# USBHUB_USB2512.net
KiCad netlist of a schematic drawn in Altium Designer
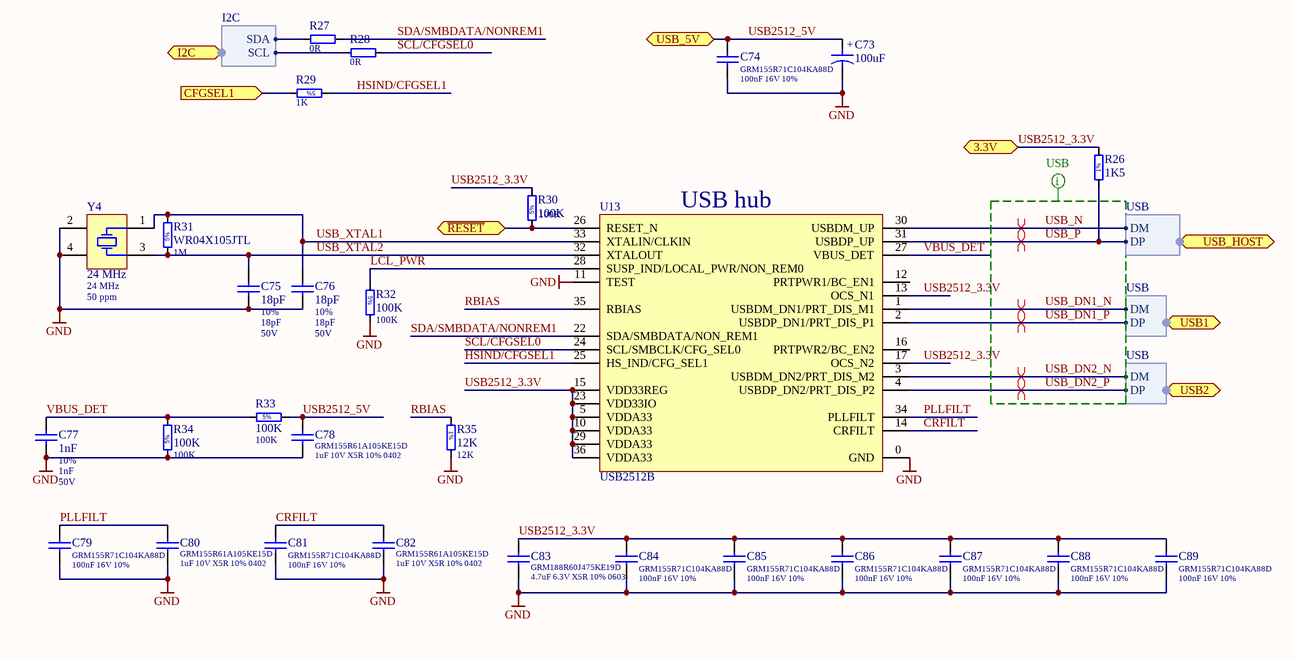
[diagram p0: USBHUB_USB2512.SchDoc]

(export (version "E")
  (design (tool "Eeschema 10.0.6"))
  (components
    (comp (ref "C73")
      (value "100uF")
      (footprint "TANTALUM:C")
      (description "Polarized capacitor")
      (fields (field (name "VOLTAGE") "50V") (field (name "TOLERANCE") "10%"))
      (libsource (lib "Passive") (part "CapacitorTANT"))
    )
    (comp (ref "C74")
      (value "GRM155R71C104KA88D")
      (footprint "CAP_SMD:0402")
      (description "Ceramic capacitor")
      (fields
        (field (name "VOLTAGE") "16V")
        (field (name "TOLERANCE") "10%")
        (field (name "ALTIUM_VALUE") "100nF 16V 10%")
      )
      (libsource (lib "") (part "Capacitor ceramic_1"))
    )
    (comp (ref "C75")
      (value "18pF")
      (footprint "CHIP_SMD:0402C")
      (description "Ceramic capacitor")
      (fields
        (field (name "TOLERANCE") "10%")
        (field (name "ALTIUM_VALUE") "18pF")
        (field (name "VOLTAGE") "50V")
      )
      (libsource (lib "") (part "Capacitor ceramic_1"))
    )
    (comp (ref "C76")
      (value "18pF")
      (footprint "CHIP_SMD:0402C")
      (description "Ceramic capacitor")
      (fields
        (field (name "TOLERANCE") "10%")
        (field (name "ALTIUM_VALUE") "18pF")
        (field (name "VOLTAGE") "50V")
      )
      (libsource (lib "") (part "Capacitor ceramic_1"))
    )
    (comp (ref "C77")
      (value "1nF")
      (footprint "CHIP_SMD:0402C")
      (description "Ceramic capacitor")
      (fields
        (field (name "TOLERANCE") "10%")
        (field (name "ALTIUM_VALUE") "1nF")
        (field (name "VOLTAGE") "50V")
      )
      (libsource (lib "") (part "Capacitor ceramic_1"))
    )
    (comp (ref "C78")
      (value "GRM155R61A105KE15D")
      (footprint "CAP_SMD:0402")
      (description "Ceramic capacitor")
      (fields
        (field (name "VOLTAGE") "10V")
        (field (name "TOLERANCE") "10%")
        (field (name "ALTIUM_VALUE") "1uF 10V X5R 10% ")
      )
      (libsource (lib "Passive") (part "Capacitor ceramic"))
    )
    (comp (ref "C79")
      (value "GRM155R71C104KA88D")
      (footprint "CAP_SMD:0402")
      (description "Ceramic capacitor")
      (fields
        (field (name "VOLTAGE") "16V")
        (field (name "TOLERANCE") "10%")
        (field (name "ALTIUM_VALUE") "100nF 16V 10%")
      )
      (libsource (lib "") (part "Capacitor ceramic_1"))
    )
    (comp (ref "C80")
      (value "GRM155R61A105KE15D")
      (footprint "CAP_SMD:0402")
      (description "Ceramic capacitor")
      (fields
        (field (name "VOLTAGE") "10V")
        (field (name "TOLERANCE") "10%")
        (field (name "ALTIUM_VALUE") "1uF 10V X5R 10% ")
      )
      (libsource (lib "Passive") (part "Capacitor ceramic"))
    )
    (comp (ref "C81")
      (value "GRM155R71C104KA88D")
      (footprint "CAP_SMD:0402")
      (description "Ceramic capacitor")
      (fields
        (field (name "VOLTAGE") "16V")
        (field (name "TOLERANCE") "10%")
        (field (name "ALTIUM_VALUE") "100nF 16V 10%")
      )
      (libsource (lib "") (part "Capacitor ceramic_1"))
    )
    (comp (ref "C82")
      (value "GRM155R61A105KE15D")
      (footprint "CAP_SMD:0402")
      (description "Ceramic capacitor")
      (fields
        (field (name "VOLTAGE") "10V")
        (field (name "TOLERANCE") "10%")
        (field (name "ALTIUM_VALUE") "1uF 10V X5R 10% ")
      )
      (libsource (lib "Passive") (part "Capacitor ceramic"))
    )
    (comp (ref "C83")
      (value "GRM188R60J475KE19D")
      (footprint "CAP_SMD:0603")
      (description "Ceramic capacitor")
      (fields
        (field (name "VOLTAGE") "6.3V")
        (field (name "TOLERANCE") "10%")
        (field (name "ALTIUM_VALUE") "4.7uF 6.3V X5R 10% ")
      )
      (libsource (lib "Passive") (part "Capacitor ceramic"))
    )
    (comp (ref "C84")
      (value "GRM155R71C104KA88D")
      (footprint "CAP_SMD:0402")
      (description "Ceramic capacitor")
      (fields
        (field (name "VOLTAGE") "16V")
        (field (name "TOLERANCE") "10%")
        (field (name "ALTIUM_VALUE") "100nF 16V 10%")
      )
      (libsource (lib "") (part "Capacitor ceramic_1"))
    )
    (comp (ref "C85")
      (value "GRM155R71C104KA88D")
      (footprint "CAP_SMD:0402")
      (description "Ceramic capacitor")
      (fields
        (field (name "VOLTAGE") "16V")
        (field (name "TOLERANCE") "10%")
        (field (name "ALTIUM_VALUE") "100nF 16V 10%")
      )
      (libsource (lib "") (part "Capacitor ceramic_1"))
    )
    (comp (ref "C86")
      (value "GRM155R71C104KA88D")
      (footprint "CAP_SMD:0402")
      (description "Ceramic capacitor")
      (fields
        (field (name "VOLTAGE") "16V")
        (field (name "TOLERANCE") "10%")
        (field (name "ALTIUM_VALUE") "100nF 16V 10%")
      )
      (libsource (lib "") (part "Capacitor ceramic_1"))
    )
    (comp (ref "C87")
      (value "GRM155R71C104KA88D")
      (footprint "CAP_SMD:0402")
      (description "Ceramic capacitor")
      (fields
        (field (name "VOLTAGE") "16V")
        (field (name "TOLERANCE") "10%")
        (field (name "ALTIUM_VALUE") "100nF 16V 10%")
      )
      (libsource (lib "") (part "Capacitor ceramic_1"))
    )
    (comp (ref "C88")
      (value "GRM155R71C104KA88D")
      (footprint "CAP_SMD:0402")
      (description "Ceramic capacitor")
      (fields
        (field (name "VOLTAGE") "16V")
        (field (name "TOLERANCE") "10%")
        (field (name "ALTIUM_VALUE") "100nF 16V 10%")
      )
      (libsource (lib "") (part "Capacitor ceramic_1"))
    )
    (comp (ref "C89")
      (value "GRM155R71C104KA88D")
      (footprint "CAP_SMD:0402")
      (description "Ceramic capacitor")
      (fields
        (field (name "VOLTAGE") "16V")
        (field (name "TOLERANCE") "10%")
        (field (name "ALTIUM_VALUE") "100nF 16V 10%")
      )
      (libsource (lib "") (part "Capacitor ceramic_1"))
    )
    (comp (ref "R26")
      (value "1K5")
      (footprint "CHIP_SMD:0402R")
      (description "Thin Film Chip Resistor")
      (fields (field (name "POWER") "0.1 W") (field (name "TOLERANCE") "1%"))
      (libsource (lib "Passive") (part "Resistor 1%"))
    )
    (comp (ref "R27")
      (value "0R")
      (footprint "CHIP_SMD:0402R")
      (description "Thin Film Resistor Jumper")
      (fields (field (name "POWER") "0.1 W") (field (name "Comment") "Resistor jumper"))
      (libsource (lib "Passive") (part "Resistor jumper"))
    )
    (comp (ref "R28")
      (value "0R")
      (footprint "CHIP_SMD:0402R")
      (description "Thin Film Resistor Jumper")
      (fields (field (name "POWER") "0.1 W") (field (name "Comment") "Resistor jumper"))
      (libsource (lib "Passive") (part "Resistor jumper"))
    )
    (comp (ref "R29")
      (value "1K")
      (footprint "CHIP_SMD:0402R")
      (description "Thin Film Chip Resistor")
      (fields (field (name "POWER") "0.1 W") (field (name "TOLERANCE") "5%"))
      (libsource (lib "Passive") (part "Resistor"))
    )
    (comp (ref "R30")
      (value "100K")
      (footprint "CHIP_SMD:0402R")
      (description "Thin Film Chip Resistor")
      (fields
        (field (name "POWER") "0.1 W")
        (field (name "TOLERANCE") "5%")
        (field (name "ALTIUM_VALUE") "100K")
      )
      (libsource (lib "Passive") (part "Resistor"))
    )
    (comp (ref "R31")
      (value "WR04X105JTL")
      (footprint "CHIP_SMD:0402R")
      (description "Thin Film Chip Resistor")
      (fields
        (field (name "POWER") "0.1 W")
        (field (name "TOLERANCE") "5%")
        (field (name "ALTIUM_VALUE") "1M")
      )
      (libsource (lib "Passive") (part "Resistor"))
    )
    (comp (ref "R32")
      (value "100K")
      (footprint "CHIP_SMD:0402R")
      (description "Thin Film Chip Resistor")
      (fields
        (field (name "POWER") "0.1 W")
        (field (name "TOLERANCE") "5%")
        (field (name "ALTIUM_VALUE") "100K")
      )
      (libsource (lib "Passive") (part "Resistor"))
    )
    (comp (ref "R33")
      (value "100K")
      (footprint "CHIP_SMD:0402R")
      (description "Thin Film Chip Resistor")
      (fields
        (field (name "POWER") "0.1 W")
        (field (name "TOLERANCE") "5%")
        (field (name "ALTIUM_VALUE") "100K")
      )
      (libsource (lib "Passive") (part "Resistor"))
    )
    (comp (ref "R34")
      (value "100K")
      (footprint "CHIP_SMD:0402R")
      (description "Thin Film Chip Resistor")
      (fields
        (field (name "POWER") "0.1 W")
        (field (name "TOLERANCE") "5%")
        (field (name "ALTIUM_VALUE") "100K")
      )
      (libsource (lib "Passive") (part "Resistor"))
    )
    (comp (ref "R35")
      (value "12K")
      (footprint "CHIP_SMD:0402R")
      (description "Thin Film Chip Resistor")
      (fields
        (field (name "POWER") "0.1 W")
        (field (name "TOLERANCE") "1%")
        (field (name "ALTIUM_VALUE") "12K")
      )
      (libsource (lib "Passive") (part "Resistor"))
    )
    (comp (ref "U13")
      (value "USB2512B")
      (footprint "QFN_DFN:QFN-36-0.5-6x6_TP_5class")
      (description "USB 2.0 Hi-Speed Hub Controller")
      (libsource (lib "IC_USB") (part "USB2512B"))
    )
    (comp (ref "Y4")
      (value "24 MHz")
      (footprint "CRYSTAL_OSC:2025")
      (description "Quartz crystal")
      (fields (field (name "ALTIUM_VALUE") "24 MHz") (field (name "TOLERANCE") "50 ppm"))
      (libsource (lib "Crystal_Osc") (part "Quartz crystal"))
    )
  )
  (nets
    (net (code "3") (name "/CFGSEL1") (class "Default")
      (node (ref "R29") (pin "2") (pinfunction "2_2") (pintype "passive"))
    )
    (net (code "4") (name "/CRFILT") (class "Default")
      (node (ref "C81") (pin "1") (pinfunction "1_1") (pintype "passive"))
      (node (ref "C82") (pin "1") (pinfunction "1_1") (pintype "passive"))
      (node (ref "U13") (pin "14") (pinfunction "CRFILT_14") (pintype "passive"))
    )
    (net (code "5") (name "/HSIND{slash}CFGSEL1") (class "Default")
      (node (ref "R29") (pin "1") (pinfunction "1_1") (pintype "passive"))
      (node (ref "U13") (pin "25") (pinfunction "HS_IND/CFG_SEL1_25") (pintype "passive"))
    )
    (net (code "6") (name "/LCL_PWR") (class "Default")
      (node (ref "R32") (pin "1") (pinfunction "1_1") (pintype "passive"))
      (node (ref "U13") (pin "28") (pinfunction "SUSP_IND/LOCAL_PWR/NON_REM0_28") (pintype "passive"))
    )
    (net (code "7") (name "/PLLFILT") (class "Default")
      (node (ref "C79") (pin "1") (pinfunction "1_1") (pintype "passive"))
      (node (ref "C80") (pin "1") (pinfunction "1_1") (pintype "passive"))
      (node (ref "U13") (pin "34") (pinfunction "PLLFILT_34") (pintype "passive"))
    )
    (net (code "8") (name "/RBIAS") (class "Default")
      (node (ref "R35") (pin "1") (pinfunction "1_1") (pintype "passive"))
      (node (ref "U13") (pin "35") (pinfunction "RBIAS_35") (pintype "passive"))
    )
    (net (code "9") (name "/SCL") (class "Default")
      (node (ref "R28") (pin "1") (pinfunction "1_1") (pintype "passive"))
    )
    (net (code "10") (name "/SCL{slash}CFGSEL0") (class "Default")
      (node (ref "R28") (pin "2") (pinfunction "2_2") (pintype "passive"))
      (node (ref "U13") (pin "24") (pinfunction "SCL/SMBCLK/CFG_SEL0_24") (pintype "passive"))
    )
    (net (code "11") (name "/SDA") (class "Default")
      (node (ref "R27") (pin "1") (pinfunction "1_1") (pintype "passive"))
    )
    (net (code "12") (name "/SDA{slash}SMBDATA{slash}NONREM1") (class "Default")
      (node (ref "R27") (pin "2") (pinfunction "2_2") (pintype "passive"))
      (node (ref "U13") (pin "22") (pinfunction "SDA/SMBDATA/NON_REM1_22") (pintype "passive"))
    )
    (net (code "13") (name "/USB2512_3.3V") (class "Default")
      (node (ref "C83") (pin "1") (pinfunction "1_1") (pintype "passive"))
      (node (ref "C84") (pin "1") (pinfunction "1_1") (pintype "passive"))
      (node (ref "C85") (pin "1") (pinfunction "1_1") (pintype "passive"))
      (node (ref "C86") (pin "1") (pinfunction "1_1") (pintype "passive"))
      (node (ref "C87") (pin "1") (pinfunction "1_1") (pintype "passive"))
      (node (ref "C88") (pin "1") (pinfunction "1_1") (pintype "passive"))
      (node (ref "C89") (pin "1") (pinfunction "1_1") (pintype "passive"))
      (node (ref "R26") (pin "2") (pinfunction "2_2") (pintype "passive"))
      (node (ref "R30") (pin "2") (pinfunction "2_2") (pintype "passive"))
      (node (ref "U13") (pin "10") (pinfunction "VDDA33_10") (pintype "passive"))
      (node (ref "U13") (pin "13") (pinfunction "OCS_N1_13") (pintype "passive"))
      (node (ref "U13") (pin "15") (pinfunction "VDD33REG_15") (pintype "passive"))
      (node (ref "U13") (pin "17") (pinfunction "OCS_N2_17") (pintype "passive"))
      (node (ref "U13") (pin "23") (pinfunction "VDD33IO_23") (pintype "passive"))
      (node (ref "U13") (pin "29") (pinfunction "VDDA33_29") (pintype "passive"))
      (node (ref "U13") (pin "36") (pinfunction "VDDA33_36") (pintype "passive"))
      (node (ref "U13") (pin "5") (pinfunction "VDDA33_5") (pintype "passive"))
    )
    (net (code "14") (name "/USB2512_5V") (class "Default")
      (node (ref "C73") (pin "1") (pinfunction "1_1") (pintype "passive"))
      (node (ref "C74") (pin "1") (pinfunction "1_1") (pintype "passive"))
      (node (ref "C78") (pin "1") (pinfunction "1_1") (pintype "passive"))
      (node (ref "R33") (pin "2") (pinfunction "2_2") (pintype "passive"))
    )
    (net (code "15") (name "/USB_DN1_N") (class "Default")
      (node (ref "U13") (pin "1") (pinfunction "USBDM_DN1/PRT_DIS_M1_1") (pintype "passive"))
    )
    (net (code "16") (name "/USB_DN1_P") (class "Default")
      (node (ref "U13") (pin "2") (pinfunction "USBDP_DN1/PRT_DIS_P1_2") (pintype "passive"))
    )
    (net (code "17") (name "/USB_DN2_N") (class "Default")
      (node (ref "U13") (pin "3") (pinfunction "USBDM_DN2/PRT_DIS_M2_3") (pintype "passive"))
    )
    (net (code "18") (name "/USB_DN2_P") (class "Default")
      (node (ref "U13") (pin "4") (pinfunction "USBDP_DN2/PRT_DIS_P2_4") (pintype "passive"))
    )
    (net (code "19") (name "/USB_N") (class "Default")
      (node (ref "U13") (pin "30") (pinfunction "USBDM_UP_30") (pintype "passive"))
    )
    (net (code "20") (name "/USB_P") (class "Default")
      (node (ref "R26") (pin "1") (pinfunction "1_1") (pintype "passive"))
      (node (ref "U13") (pin "31") (pinfunction "USBDP_UP_31") (pintype "passive"))
    )
    (net (code "21") (name "/USB_XTAL1") (class "Default")
      (node (ref "C76") (pin "2") (pinfunction "2_2") (pintype "passive"))
      (node (ref "R31") (pin "2") (pinfunction "2_2") (pintype "passive"))
      (node (ref "U13") (pin "33") (pinfunction "XTALIN/CLKIN_33") (pintype "passive"))
      (node (ref "Y4") (pin "1") (pinfunction "X_1") (pintype "passive"))
    )
    (net (code "22") (name "/USB_XTAL2") (class "Default")
      (node (ref "C75") (pin "2") (pinfunction "2_2") (pintype "passive"))
      (node (ref "R31") (pin "1") (pinfunction "1_1") (pintype "passive"))
      (node (ref "U13") (pin "32") (pinfunction "XTALOUT_32") (pintype "passive"))
      (node (ref "Y4") (pin "3") (pinfunction "X_3") (pintype "passive"))
    )
    (net (code "23") (name "/VBUS_DET") (class "Default")
      (node (ref "C77") (pin "2") (pinfunction "2_2") (pintype "passive"))
      (node (ref "R33") (pin "1") (pinfunction "1_1") (pintype "passive"))
      (node (ref "R34") (pin "2") (pinfunction "2_2") (pintype "passive"))
      (node (ref "U13") (pin "27") (pinfunction "VBUS_DET_27") (pintype "passive"))
    )
    (net (code "26") (name "/~{RESET}") (class "Default")
      (node (ref "R30") (pin "1") (pinfunction "1_1") (pintype "passive"))
      (node (ref "U13") (pin "26") (pinfunction "RESET_N_26") (pintype "passive"))
    )
    (net (code "27") (name "GND") (class "Default")
      (node (ref "C73") (pin "2") (pinfunction "2_2") (pintype "passive"))
      (node (ref "C74") (pin "2") (pinfunction "2_2") (pintype "passive"))
      (node (ref "C75") (pin "1") (pinfunction "1_1") (pintype "passive"))
      (node (ref "C76") (pin "1") (pinfunction "1_1") (pintype "passive"))
      (node (ref "C77") (pin "1") (pinfunction "1_1") (pintype "passive"))
      (node (ref "C78") (pin "2") (pinfunction "2_2") (pintype "passive"))
      (node (ref "C79") (pin "2") (pinfunction "2_2") (pintype "passive"))
      (node (ref "C80") (pin "2") (pinfunction "2_2") (pintype "passive"))
      (node (ref "C81") (pin "2") (pinfunction "2_2") (pintype "passive"))
      (node (ref "C82") (pin "2") (pinfunction "2_2") (pintype "passive"))
      (node (ref "C83") (pin "2") (pinfunction "2_2") (pintype "passive"))
      (node (ref "C84") (pin "2") (pinfunction "2_2") (pintype "passive"))
      (node (ref "C85") (pin "2") (pinfunction "2_2") (pintype "passive"))
      (node (ref "C86") (pin "2") (pinfunction "2_2") (pintype "passive"))
      (node (ref "C87") (pin "2") (pinfunction "2_2") (pintype "passive"))
      (node (ref "C88") (pin "2") (pinfunction "2_2") (pintype "passive"))
      (node (ref "C89") (pin "2") (pinfunction "2_2") (pintype "passive"))
      (node (ref "R32") (pin "2") (pinfunction "2_2") (pintype "passive"))
      (node (ref "R34") (pin "1") (pinfunction "1_1") (pintype "passive"))
      (node (ref "R35") (pin "2") (pinfunction "2_2") (pintype "passive"))
      (node (ref "U13") (pin "0") (pinfunction "GND_0") (pintype "passive"))
      (node (ref "U13") (pin "11") (pinfunction "TEST_11") (pintype "passive"))
      (node (ref "Y4") (pin "2") (pinfunction "GND_2") (pintype "power_in"))
      (node (ref "Y4") (pin "4") (pinfunction "GND_4") (pintype "power_in"))
    )
    (net (code "28") (name "unconnected-(U13-PRTPWR1{slash}BC_EN1-Pad12)") (class "Default")
      (node (ref "U13") (pin "12") (pinfunction "PRTPWR1/BC_EN1_12") (pintype "passive"))
    )
    (net (code "29") (name "unconnected-(U13-PRTPWR2{slash}BC_EN2-Pad16)") (class "Default")
      (node (ref "U13") (pin "16") (pinfunction "PRTPWR2/BC_EN2_16") (pintype "passive"))
    )
  )
)
